# Connectors.net
KiCad netlist of a schematic drawn in Altium Designer
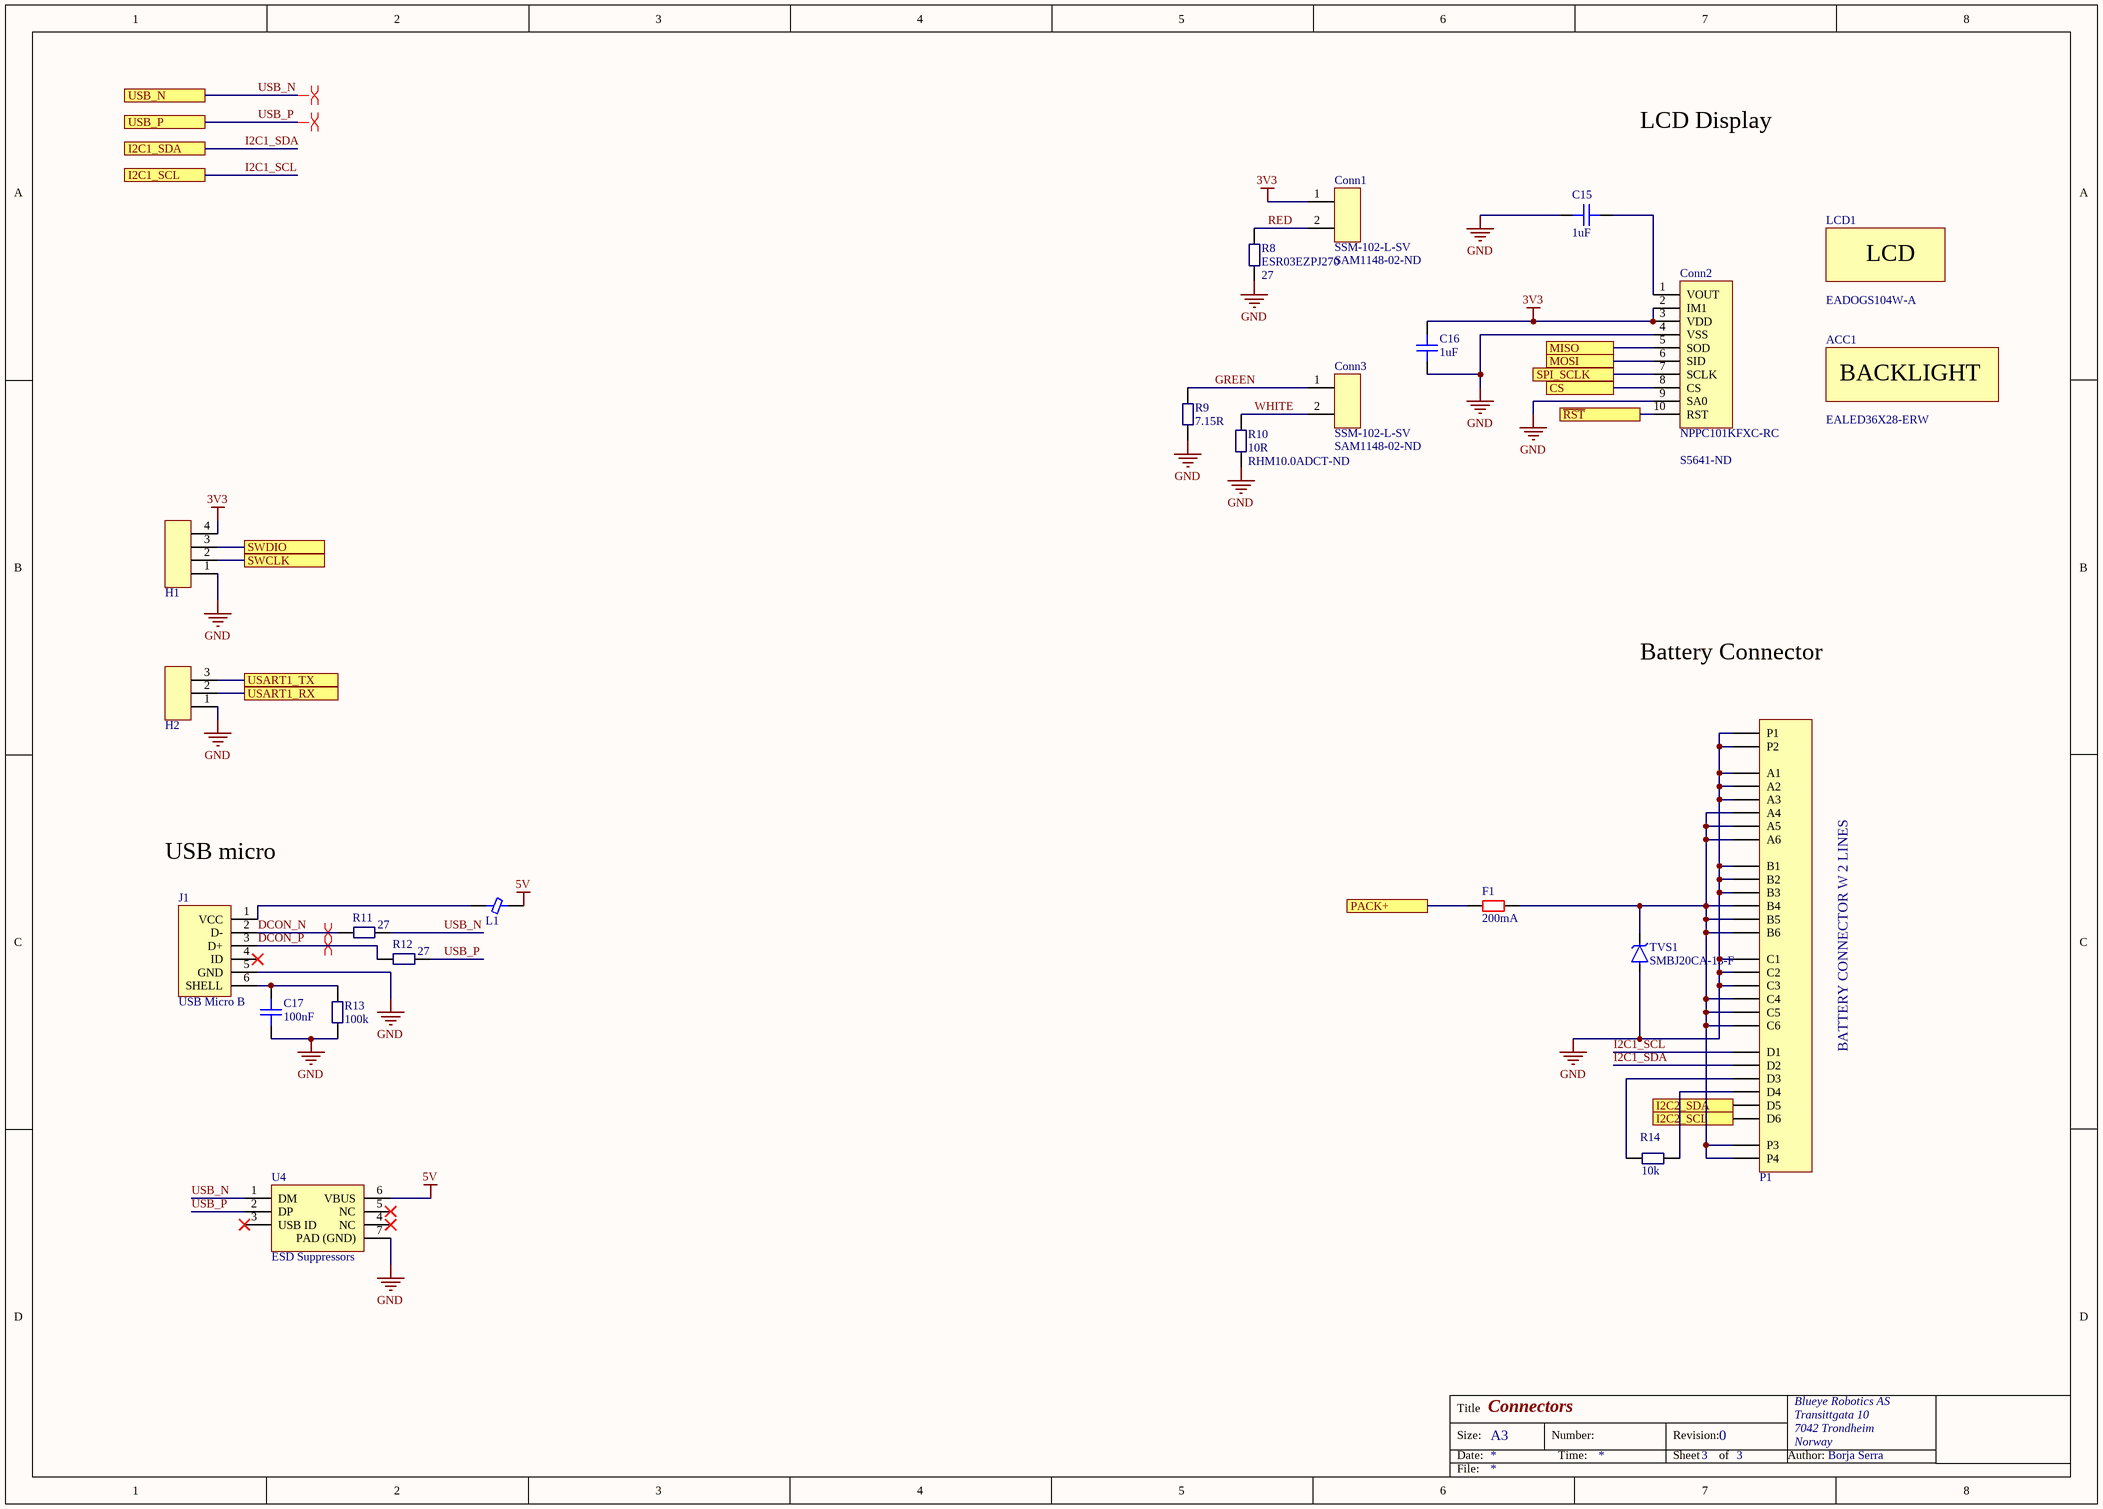
[diagram p0: Connectors.SchDoc]

(export (version "E")
  (design (tool "Eeschema 10.0.6"))
  (components
    (comp (ref "ACC1")
      (value "~")
      (description "LED BACKLIT F. EA DOGS104")
      (fields (field (name "MANUFACTURER PART NUMBER 1") "EALED36X28-ERW"))
      (libsource (lib "Battery Reader") (part "LED BACKLIT F. EA DOGS104"))
    )
    (comp (ref "C15")
      (value "1uF")
      (footprint "1206 CAPACITOR")
      (description "Multilayer Ceramic Capacitors MLCC - SMD/SMT 1206 1.0uF 50V X7R 20%")
      (fields (field (name "MANUFACTURER") "TDK") (field (name "MPN") "C3216X7R1H105M160AB"))
      (libsource (lib "Battery Reader") (part "Capacitor 1uF 50V"))
    )
    (comp (ref "C16")
      (value "1uF")
      (footprint "1206 CAPACITOR")
      (description "Multilayer Ceramic Capacitors MLCC - SMD/SMT 1206 1.0uF 50V X7R 20%")
      (fields (field (name "MANUFACTURER") "TDK") (field (name "MPN") "C3216X7R1H105M160AB"))
      (libsource (lib "Battery Reader") (part "Capacitor 1uF 50V"))
    )
    (comp (ref "C17")
      (value "100nF")
      (footprint "0603 Capacitor")
      (description "CAP CER 0.1UF 50V X7R 0603")
      (fields
        (field (name "MPN") "CL10B104KB8NNNC")
        (field (name "MANUFACTURER") "Samsung Electro-Mechanics")
      )
      (libsource (lib "Battery Reader") (part "CAP CER 0.1UF 50V X7R 0603"))
    )
    (comp (ref "Conn1")
      (value "SSM-102-L-SV")
      (footprint "CON2_1X2_DU_SSM")
      (description "CONN RCPT .100\" 2POS SNGL VERT")
      (fields (field (name "SUPPLIER PART NUMBER 1") "SAM1148-02-ND"))
      (libsource (lib "Battery Reader") (part "CONN RCPT .100{dblquote} 2POS SNGL VERT"))
    )
    (comp (ref "Conn2")
      (value "NPPC101KFXC-RC")
      (footprint "CONN FMALE 10POS .1\" SMD GOLD")
      (description "CONN FMALE 10POS .1\" SMD GOLD")
      (fields (field (name "SUPPLIER PART NUMBER 1") "S5641-ND"))
      (libsource (lib "Battery Reader") (part "CONN FMALE 10POS .1{dblquote} SMD GOLD"))
    )
    (comp (ref "Conn3")
      (value "SSM-102-L-SV")
      (footprint "CON2_1X2_DU_SSM")
      (description "CONN RCPT .100\" 2POS SNGL VERT")
      (fields (field (name "SUPPLIER PART NUMBER 1") "SAM1148-02-ND"))
      (libsource (lib "Battery Reader") (part "CONN RCPT .100{dblquote} 2POS SNGL VERT"))
    )
    (comp (ref "F1")
      (value "200mA")
      (footprint "0603 Resistor")
      (fields (field (name "MPN") "F0603G0R20FNTR") (field (name "MANUFACTURER") "AVX Corporation"))
      (libsource (lib "Battery Reader") (part "Fuse 200mA 0603"))
    )
    (comp (ref "H1")
      (value "Header 4pin SMD")
      (footprint "Header 4pos 100 mil SMD")
      (description "CONN HEADER 4POS VERT 2.54MM SMD")
      (fields (field (name "MANUFACTURER") "Molex, LLC") (field (name "MPN") "0878980426"))
      (libsource (lib "Battery Reader") (part "Header 4pin SMD"))
    )
    (comp (ref "H2")
      (value "Header 3pin SMD")
      (footprint "Header 3pos 100 mil SMD")
      (description "3 Positions Header, Breakaway Connector 0.100\" (2.54mm) Surface Mount Tin")
      (fields (field (name "MANUFACTURER") "Molex, LLC") (field (name "MPN") "0878980306"))
      (libsource (lib "Battery Reader") (part "Header 3pin SMD"))
    )
    (comp (ref "J1")
      (value "USB Micro B")
      (footprint "10118193-0001LF Micro USB")
      (description "USB Connectors 5P MICRO USB TYPE B RECEPTACLE W/ PEGS")
      (fields (field (name "MANUFACTURER") "Amphenol FCI") (field (name "MPN") "10118193-0001LF"))
      (libsource (lib "Battery Reader") (part "USB Micro B"))
    )
    (comp (ref "L1")
      (value "60 OHM")
      (footprint "0805 Capacitor")
      (description "FERRITE BEAD 60 OHM 0805 1LN")
      (fields (field (name "MANUFACTURER") "Taiyo Yuden") (field (name "MPN") "BKP2125HS600-T"))
      (libsource (lib "Battery Reader") (part "FERRITE BEAD 60 ohm"))
    )
    (comp (ref "LCD1")
      (value "~")
      (description "4X10 DOG CHARACTERDISPLAY")
      (fields (field (name "MANUFACTURER PART NUMBER 1") "EADOGS104W-A"))
      (libsource (lib "Battery Reader") (part "4X10 DOG CHARACTERDISPLAY"))
    )
    (comp (ref "P1")
      (value "MPTC-02-24-02-6.30-XX-X-V-LC")
      (footprint "MPTC-02-24-02-6.30-XX-X-V-LC")
      (description "Samtec PowerStrip 30A Signal/Power Combo Connector")
      (fields (field (name "MPN") "MPTC-02-24-02-6.30-01-L-V") (field (name "MANUFACTURER") "Samtec"))
      (libsource (lib "P2-Adapter-ver1") (part "MPTC-02-24-02-6.30-XX-X-V-LC"))
    )
    (comp (ref "R8")
      (value "ESR03EZPJ270")
      (footprint "0603 Resistor")
      (description "RES SMD 27 OHM 5% 1/4W 0603")
      (fields (field (name "ALTIUM_VALUE") "27") (field (name "TOLERANCE") "5%"))
      (libsource (lib "Battery Reader") (part "RES SMD 27 OHM 5% 1/4W 0603"))
    )
    (comp (ref "R9")
      (value "CRCW06037R15FKEA")
      (footprint "0603 Resistor")
      (description "RES SMD 7.15 OHM 1% 1/10W 0603")
      (fields (field (name "TOLERANCE") "1%") (field (name "RESISTANCE") "7.15R"))
      (libsource (lib "Battery Reader") (part "RES SMD 7.15 OHM 1% 1/10W 0603"))
    )
    (comp (ref "R10")
      (value "10R")
      (footprint "0603 Resistor")
      (description "RES SMD 10 OHM 5% 1/4W 0603")
      (fields
        (field (name "MANUFACTURER") "Rohm Semiconductor")
        (field (name "MPN") "ESR03EZPF10R0")
        (field (name "SUPPLIER PART NUMBER 1") "RHM10.0ADCT-ND")
      )
      (libsource (lib "Battery Reader") (part "RES SMD 10 OHM 5% 1/4W 0603"))
    )
    (comp (ref "R11")
      (value "27")
      (footprint "0603 Resistor")
      (description "RES SMD 27 OHM 5% 1/4W 0603")
      (fields (field (name "MPN") "ESR03EZPJ270") (field (name "TOLERANCE") "5%"))
      (libsource (lib "Battery Reader") (part "RES SMD 27 OHM 5% 1/4W 0603"))
    )
    (comp (ref "R12")
      (value "27")
      (footprint "0603 Resistor")
      (description "RES SMD 27 OHM 5% 1/4W 0603")
      (fields (field (name "MPN") "ESR03EZPJ270") (field (name "TOLERANCE") "5%"))
      (libsource (lib "Battery Reader") (part "RES SMD 27 OHM 5% 1/4W 0603"))
    )
    (comp (ref "R13")
      (value "100k")
      (footprint "0603 Resistor")
      (description "RES SMD 100K OHM 5% 1/10W 0603")
      (fields (field (name "MANUFACTURER") "Yageo") (field (name "MPN") "RC0603JR-07100KL"))
      (libsource (lib "Battery Reader") (part "RES SMD 100K OHM 5% 1/10W 0603"))
    )
    (comp (ref "R14")
      (value "10k")
      (footprint "0603 Resistor")
      (description "RES SMD 10K OHM 5% 1/10W 0603")
      (fields (field (name "MANUFACTURER") "Yageo") (field (name "MPN") "RC0603JR-0710KL"))
      (libsource (lib "P2-Adapter-ver1") (part "RES SMD 10K OHM 5% 1/10W 0603"))
    )
    (comp (ref "TVS1")
      (value "SMBJ20CA-13-F")
      (footprint "TVS diode")
      (description "TVS DIODE 20VWM 32.4VC SMA")
      (fields (field (name "MANUFACTURER") "Diodes Incorporated"))
      (libsource (lib "P2-Adapter-ver1") (part "TVS 20V"))
    )
    (comp (ref "U4")
      (value "ESD Suppressors")
      (footprint "RCLAMP0854P.TCT - SON50P160X65_HS-7N")
      (description "ESD Suppressors RCLAMP0854P 4LINES 8V SLP")
      (fields (field (name "MANUFACTURER") "Semtech") (field (name "MPN") "RCLAMP0854P.TCT"))
      (libsource (lib "Battery Reader") (part "ESD Suppressors"))
    )
  )
  (nets
    (net (code "1") (name "/CS") (class "Default")
      (node (ref "Conn2") (pin "8") (pinfunction "CS_8") (pintype "passive"))
    )
    (net (code "2") (name "/DCON_N") (class "Default")
      (node (ref "J1") (pin "2") (pinfunction "D-_2") (pintype "passive"))
      (node (ref "R11") (pin "1") (pinfunction "1_1") (pintype "passive"))
    )
    (net (code "3") (name "/DCON_P") (class "Default")
      (node (ref "J1") (pin "3") (pinfunction "D+_3") (pintype "passive"))
      (node (ref "R12") (pin "1") (pinfunction "1_1") (pintype "passive"))
    )
    (net (code "4") (name "/GREEN") (class "Default")
      (node (ref "Conn3") (pin "1") (pintype "passive"))
      (node (ref "R9") (pin "2") (pinfunction "2_2") (pintype "passive"))
    )
    (net (code "5") (name "/I2C1_SCL") (class "Default")
      (node (ref "P1") (pin "D1") (pinfunction "D1_D1") (pintype "passive"))
    )
    (net (code "6") (name "/I2C1_SDA") (class "Default")
      (node (ref "P1") (pin "D2") (pinfunction "D2_D2") (pintype "passive"))
    )
    (net (code "7") (name "/I2C2_SCL") (class "Default")
      (node (ref "P1") (pin "D6") (pinfunction "D6_D6") (pintype "passive"))
    )
    (net (code "8") (name "/I2C2_SDA") (class "Default")
      (node (ref "P1") (pin "D5") (pinfunction "D5_D5") (pintype "passive"))
    )
    (net (code "9") (name "/MISO") (class "Default")
      (node (ref "Conn2") (pin "5") (pinfunction "SOD_5") (pintype "passive"))
    )
    (net (code "10") (name "/MOSI") (class "Default")
      (node (ref "Conn2") (pin "6") (pinfunction "SID_6") (pintype "passive"))
    )
    (net (code "11") (name "/PACK+") (class "Default")
      (node (ref "F1") (pin "1") (pinfunction "1_1") (pintype "passive"))
    )
    (net (code "12") (name "/RED") (class "Default")
      (node (ref "Conn1") (pin "2") (pintype "passive"))
      (node (ref "R8") (pin "2") (pinfunction "2_2") (pintype "passive"))
    )
    (net (code "13") (name "/SPI_SCLK") (class "Default")
      (node (ref "Conn2") (pin "7") (pinfunction "SCLK_7") (pintype "passive"))
    )
    (net (code "14") (name "/SWCLK") (class "Default")
      (node (ref "H1") (pin "2") (pinfunction "2_2") (pintype "passive"))
    )
    (net (code "15") (name "/SWDIO") (class "Default")
      (node (ref "H1") (pin "3") (pinfunction "3_3") (pintype "passive"))
    )
    (net (code "16") (name "/USART1_RX") (class "Default") (node (ref "H2") (pin "2") (pintype "passive")))
    (net (code "17") (name "/USART1_TX") (class "Default") (node (ref "H2") (pin "3") (pintype "passive")))
    (net (code "18") (name "/USB_N") (class "Default")
      (node (ref "R11") (pin "2") (pinfunction "2_2") (pintype "passive"))
      (node (ref "U4") (pin "1") (pinfunction "DM_1") (pintype "passive"))
    )
    (net (code "19") (name "/USB_P") (class "Default")
      (node (ref "R12") (pin "2") (pinfunction "2_2") (pintype "passive"))
      (node (ref "U4") (pin "2") (pinfunction "DP_2") (pintype "passive"))
    )
    (net (code "20") (name "/WHITE") (class "Default")
      (node (ref "Conn3") (pin "2") (pintype "passive"))
      (node (ref "R10") (pin "2") (pinfunction "2_2") (pintype "passive"))
    )
    (net (code "21") (name "/~{RST}") (class "Default")
      (node (ref "Conn2") (pin "10") (pinfunction "RST_10") (pintype "passive"))
    )
    (net (code "22") (name "3V3") (class "Default")
      (node (ref "C16") (pin "1") (pinfunction "1_1") (pintype "passive"))
      (node (ref "Conn1") (pin "1") (pintype "passive"))
      (node (ref "Conn2") (pin "2") (pinfunction "IM1_2") (pintype "passive"))
      (node (ref "Conn2") (pin "3") (pinfunction "VDD_3") (pintype "passive"))
      (node (ref "H1") (pin "4") (pinfunction "4_4") (pintype "passive"))
    )
    (net (code "23") (name "5V") (class "Default")
      (node (ref "L1") (pin "2") (pinfunction "L2_2") (pintype "passive"))
      (node (ref "U4") (pin "6") (pinfunction "VBUS_6") (pintype "passive"))
    )
    (net (code "24") (name "GND") (class "Default")
      (node (ref "C15") (pin "2") (pinfunction "2_2") (pintype "passive"))
      (node (ref "C16") (pin "2") (pinfunction "2_2") (pintype "passive"))
      (node (ref "C17") (pin "1") (pinfunction "1_1") (pintype "passive"))
      (node (ref "Conn2") (pin "4") (pinfunction "VSS_4") (pintype "passive"))
      (node (ref "Conn2") (pin "9") (pinfunction "SA0_9") (pintype "passive"))
      (node (ref "H1") (pin "1") (pinfunction "1_1") (pintype "passive"))
      (node (ref "H2") (pin "1") (pintype "passive"))
      (node (ref "J1") (pin "5") (pinfunction "GND_5") (pintype "passive"))
      (node (ref "P1") (pin "A1") (pinfunction "A1_A1") (pintype "passive"))
      (node (ref "P1") (pin "A2") (pinfunction "A2_A2") (pintype "passive"))
      (node (ref "P1") (pin "A3") (pinfunction "A3_A3") (pintype "passive"))
      (node (ref "P1") (pin "B1") (pinfunction "B1_B1") (pintype "passive"))
      (node (ref "P1") (pin "B2") (pinfunction "B2_B2") (pintype "passive"))
      (node (ref "P1") (pin "B3") (pinfunction "B3_B3") (pintype "passive"))
      (node (ref "P1") (pin "C1") (pinfunction "C1_C1") (pintype "passive"))
      (node (ref "P1") (pin "C2") (pinfunction "C2_C2") (pintype "passive"))
      (node (ref "P1") (pin "C3") (pinfunction "C3_C3") (pintype "passive"))
      (node (ref "P1") (pin "P1") (pinfunction "P1_P1") (pintype "passive"))
      (node (ref "P1") (pin "P2") (pinfunction "P2_P2") (pintype "passive"))
      (node (ref "R10") (pin "1") (pinfunction "1_1") (pintype "passive"))
      (node (ref "R13") (pin "1") (pinfunction "1_1") (pintype "passive"))
      (node (ref "R8") (pin "1") (pinfunction "1_1") (pintype "passive"))
      (node (ref "R9") (pin "1") (pinfunction "1_1") (pintype "passive"))
      (node (ref "TVS1") (pin "2") (pintype "passive"))
      (node (ref "U4") (pin "7") (pinfunction "PAD_(GND)_7") (pintype "passive"))
    )
    (net (code "25") (name "Net-(Conn2-VOUT)") (class "Default")
      (node (ref "C15") (pin "1") (pinfunction "1_1") (pintype "passive"))
      (node (ref "Conn2") (pin "1") (pinfunction "VOUT_1") (pintype "passive"))
    )
    (net (code "26") (name "Net-(F1-Pad2)") (class "Default")
      (node (ref "F1") (pin "2") (pinfunction "2_2") (pintype "passive"))
      (node (ref "P1") (pin "A4") (pinfunction "A4_A4") (pintype "passive"))
      (node (ref "P1") (pin "A5") (pinfunction "A5_A5") (pintype "passive"))
      (node (ref "P1") (pin "A6") (pinfunction "A6_A6") (pintype "passive"))
      (node (ref "P1") (pin "B4") (pinfunction "B4_B4") (pintype "passive"))
      (node (ref "P1") (pin "B5") (pinfunction "B5_B5") (pintype "passive"))
      (node (ref "P1") (pin "B6") (pinfunction "B6_B6") (pintype "passive"))
      (node (ref "P1") (pin "C4") (pinfunction "C4_C4") (pintype "passive"))
      (node (ref "P1") (pin "C5") (pinfunction "C5_C5") (pintype "passive"))
      (node (ref "P1") (pin "C6") (pinfunction "C6_C6") (pintype "passive"))
      (node (ref "P1") (pin "P3") (pinfunction "P3_P3") (pintype "passive"))
      (node (ref "P1") (pin "P4") (pinfunction "P4_P4") (pintype "passive"))
      (node (ref "TVS1") (pin "1") (pintype "passive"))
    )
    (net (code "27") (name "Net-(J1-SHELL)") (class "Default")
      (node (ref "C17") (pin "2") (pinfunction "2_2") (pintype "passive"))
      (node (ref "J1") (pin "6") (pinfunction "SHELL_6") (pintype "passive"))
      (node (ref "R13") (pin "2") (pinfunction "2_2") (pintype "passive"))
    )
    (net (code "28") (name "Net-(J1-VCC)") (class "Default")
      (node (ref "J1") (pin "1") (pinfunction "VCC_1") (pintype "passive"))
      (node (ref "L1") (pin "1") (pinfunction "L1_1") (pintype "passive"))
    )
    (net (code "29") (name "Net-(P1-PadD3)") (class "Default")
      (node (ref "P1") (pin "D3") (pinfunction "D3_D3") (pintype "passive"))
      (node (ref "R14") (pin "1") (pinfunction "1_1") (pintype "passive"))
    )
    (net (code "30") (name "Net-(P1-PadD4)") (class "Default")
      (node (ref "P1") (pin "D4") (pinfunction "D4_D4") (pintype "passive"))
      (node (ref "R14") (pin "2") (pinfunction "2_2") (pintype "passive"))
    )
    (net (code "31") (name "unconnected-(J1-ID-Pad4)") (class "Default")
      (node (ref "J1") (pin "4") (pinfunction "ID_4") (pintype "passive+no_connect"))
    )
    (net (code "32") (name "unconnected-(U4-NC-Pad4)") (class "Default")
      (node (ref "U4") (pin "4") (pinfunction "NC_4") (pintype "passive+no_connect"))
    )
    (net (code "33") (name "unconnected-(U4-NC-Pad5)") (class "Default")
      (node (ref "U4") (pin "5") (pinfunction "NC_5") (pintype "passive+no_connect"))
    )
    (net (code "34") (name "unconnected-(U4-USB_ID-Pad3)") (class "Default")
      (node (ref "U4") (pin "3") (pinfunction "USB_ID_3") (pintype "passive+no_connect"))
    )
  )
)
